# NAV_Doska_1.net
KiCad netlist of a schematic drawn in EAGLE
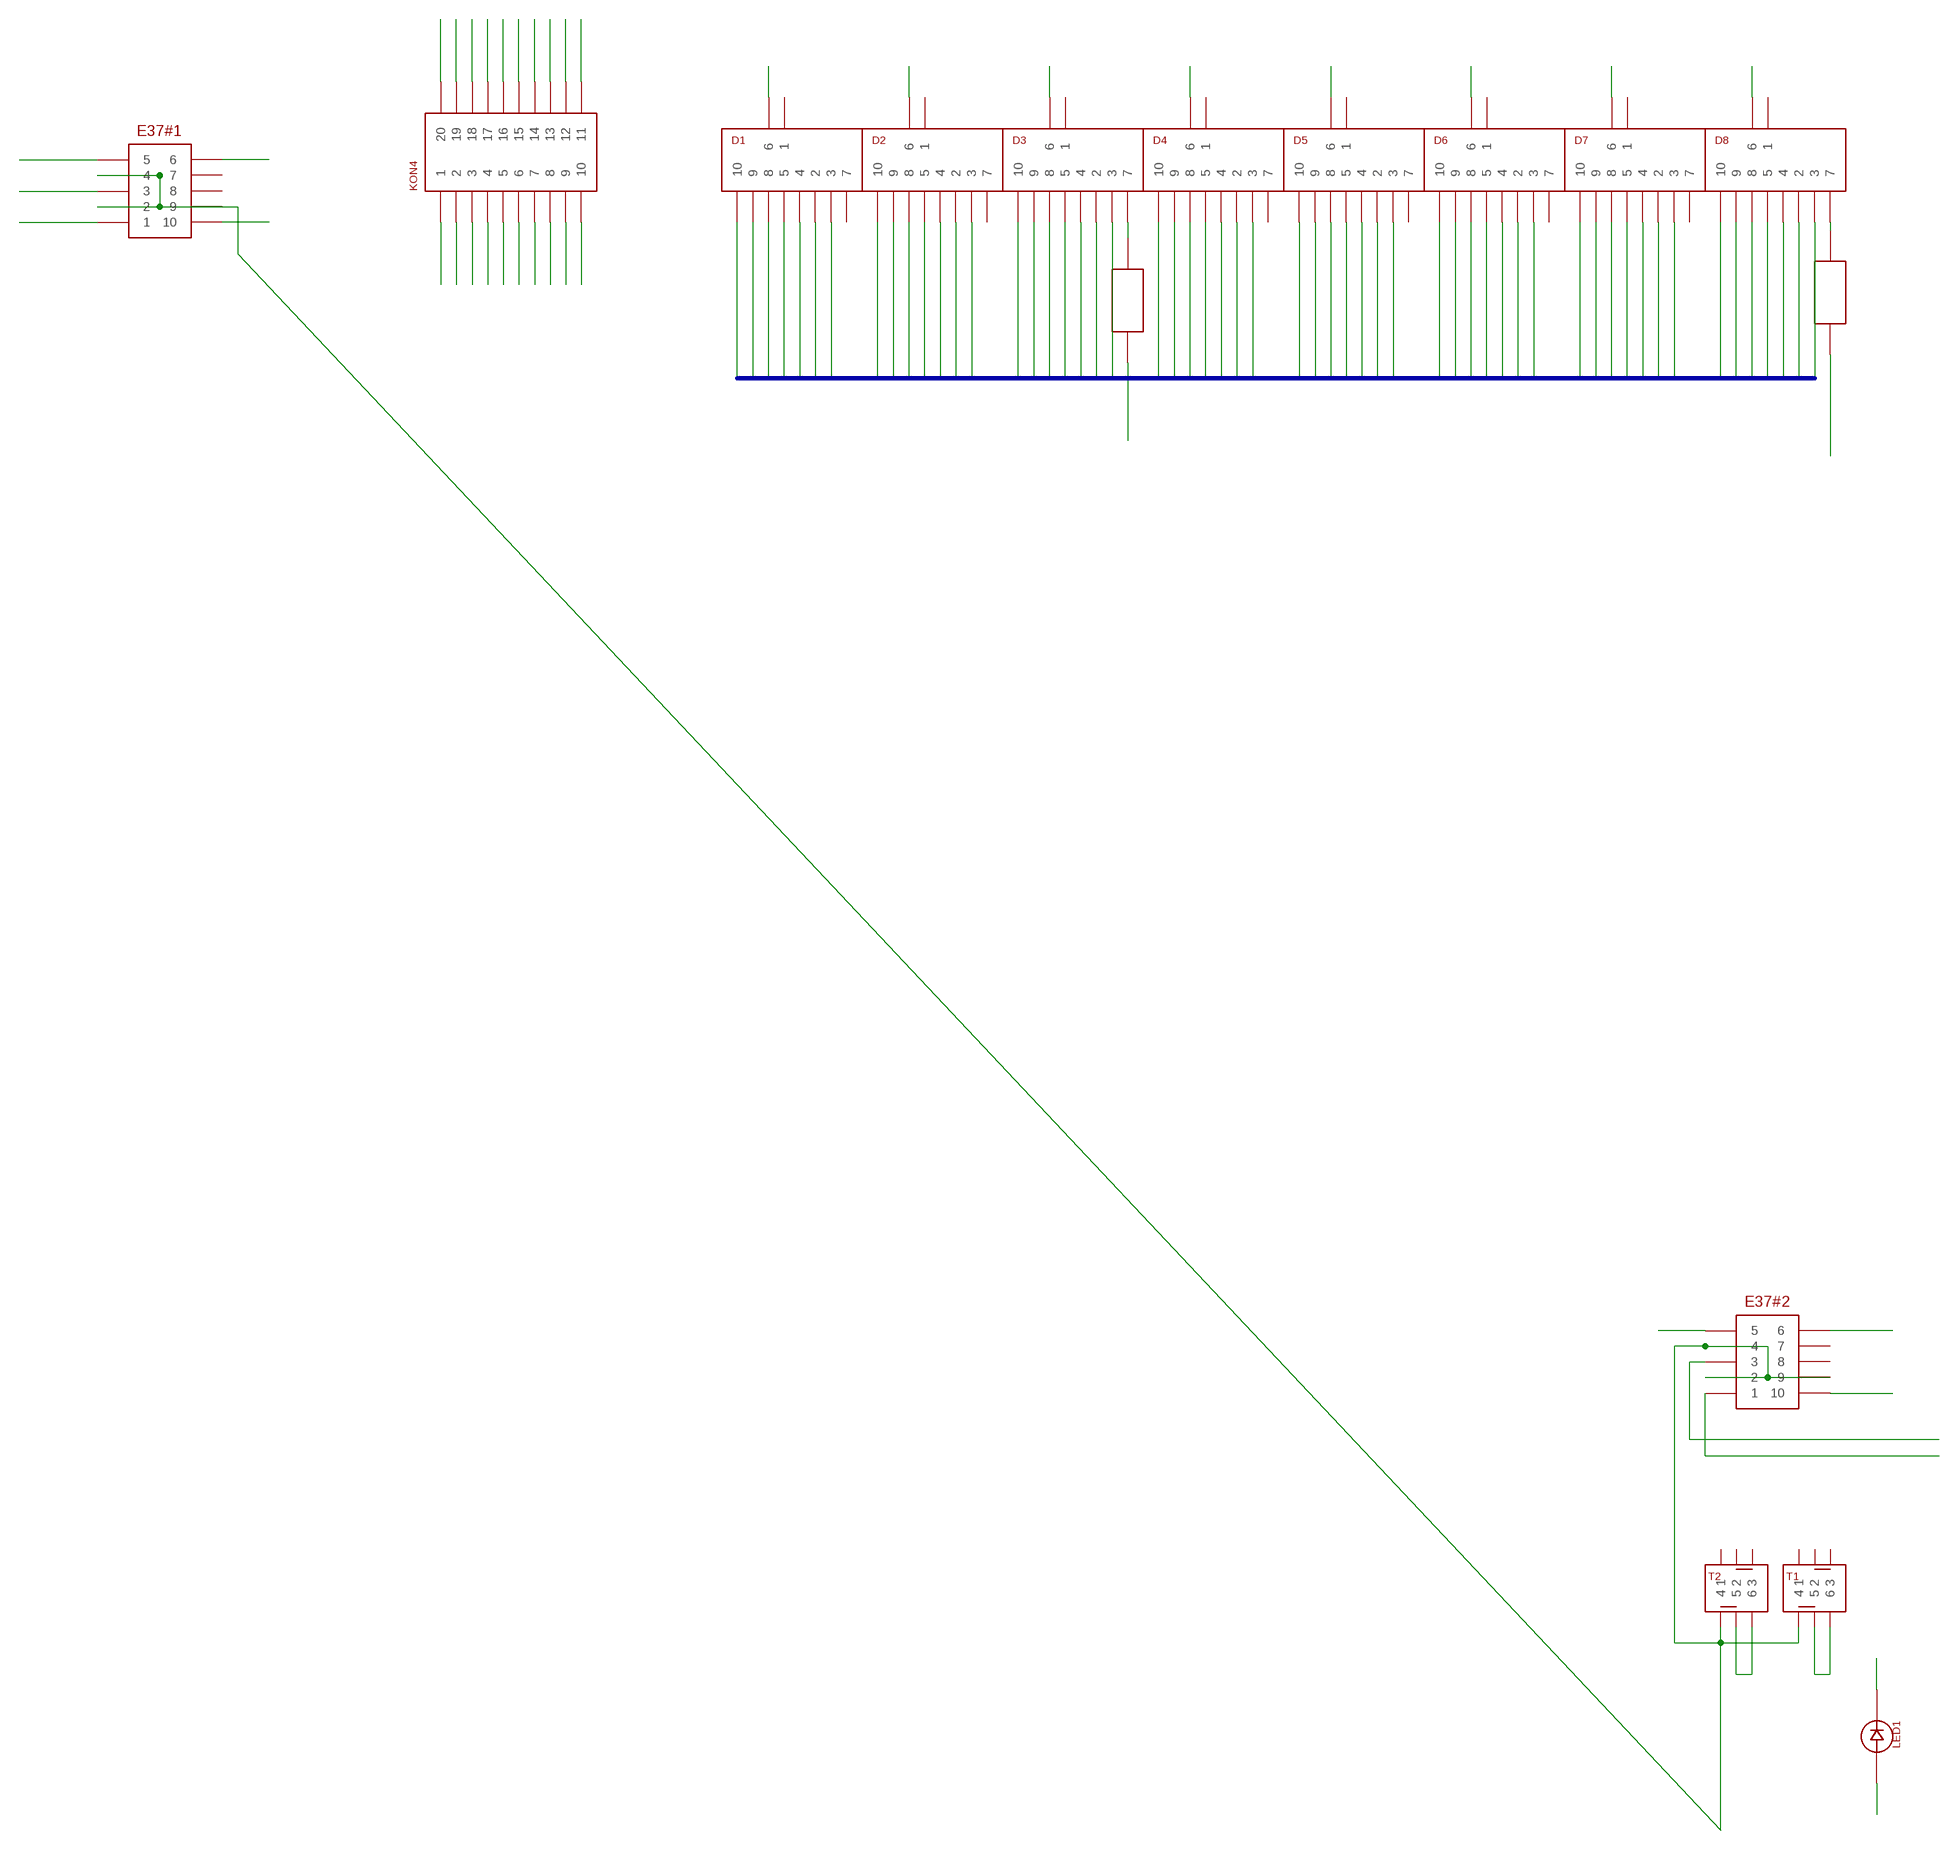
[diagram p0: schematic, sheet 1, part 1 of 2]
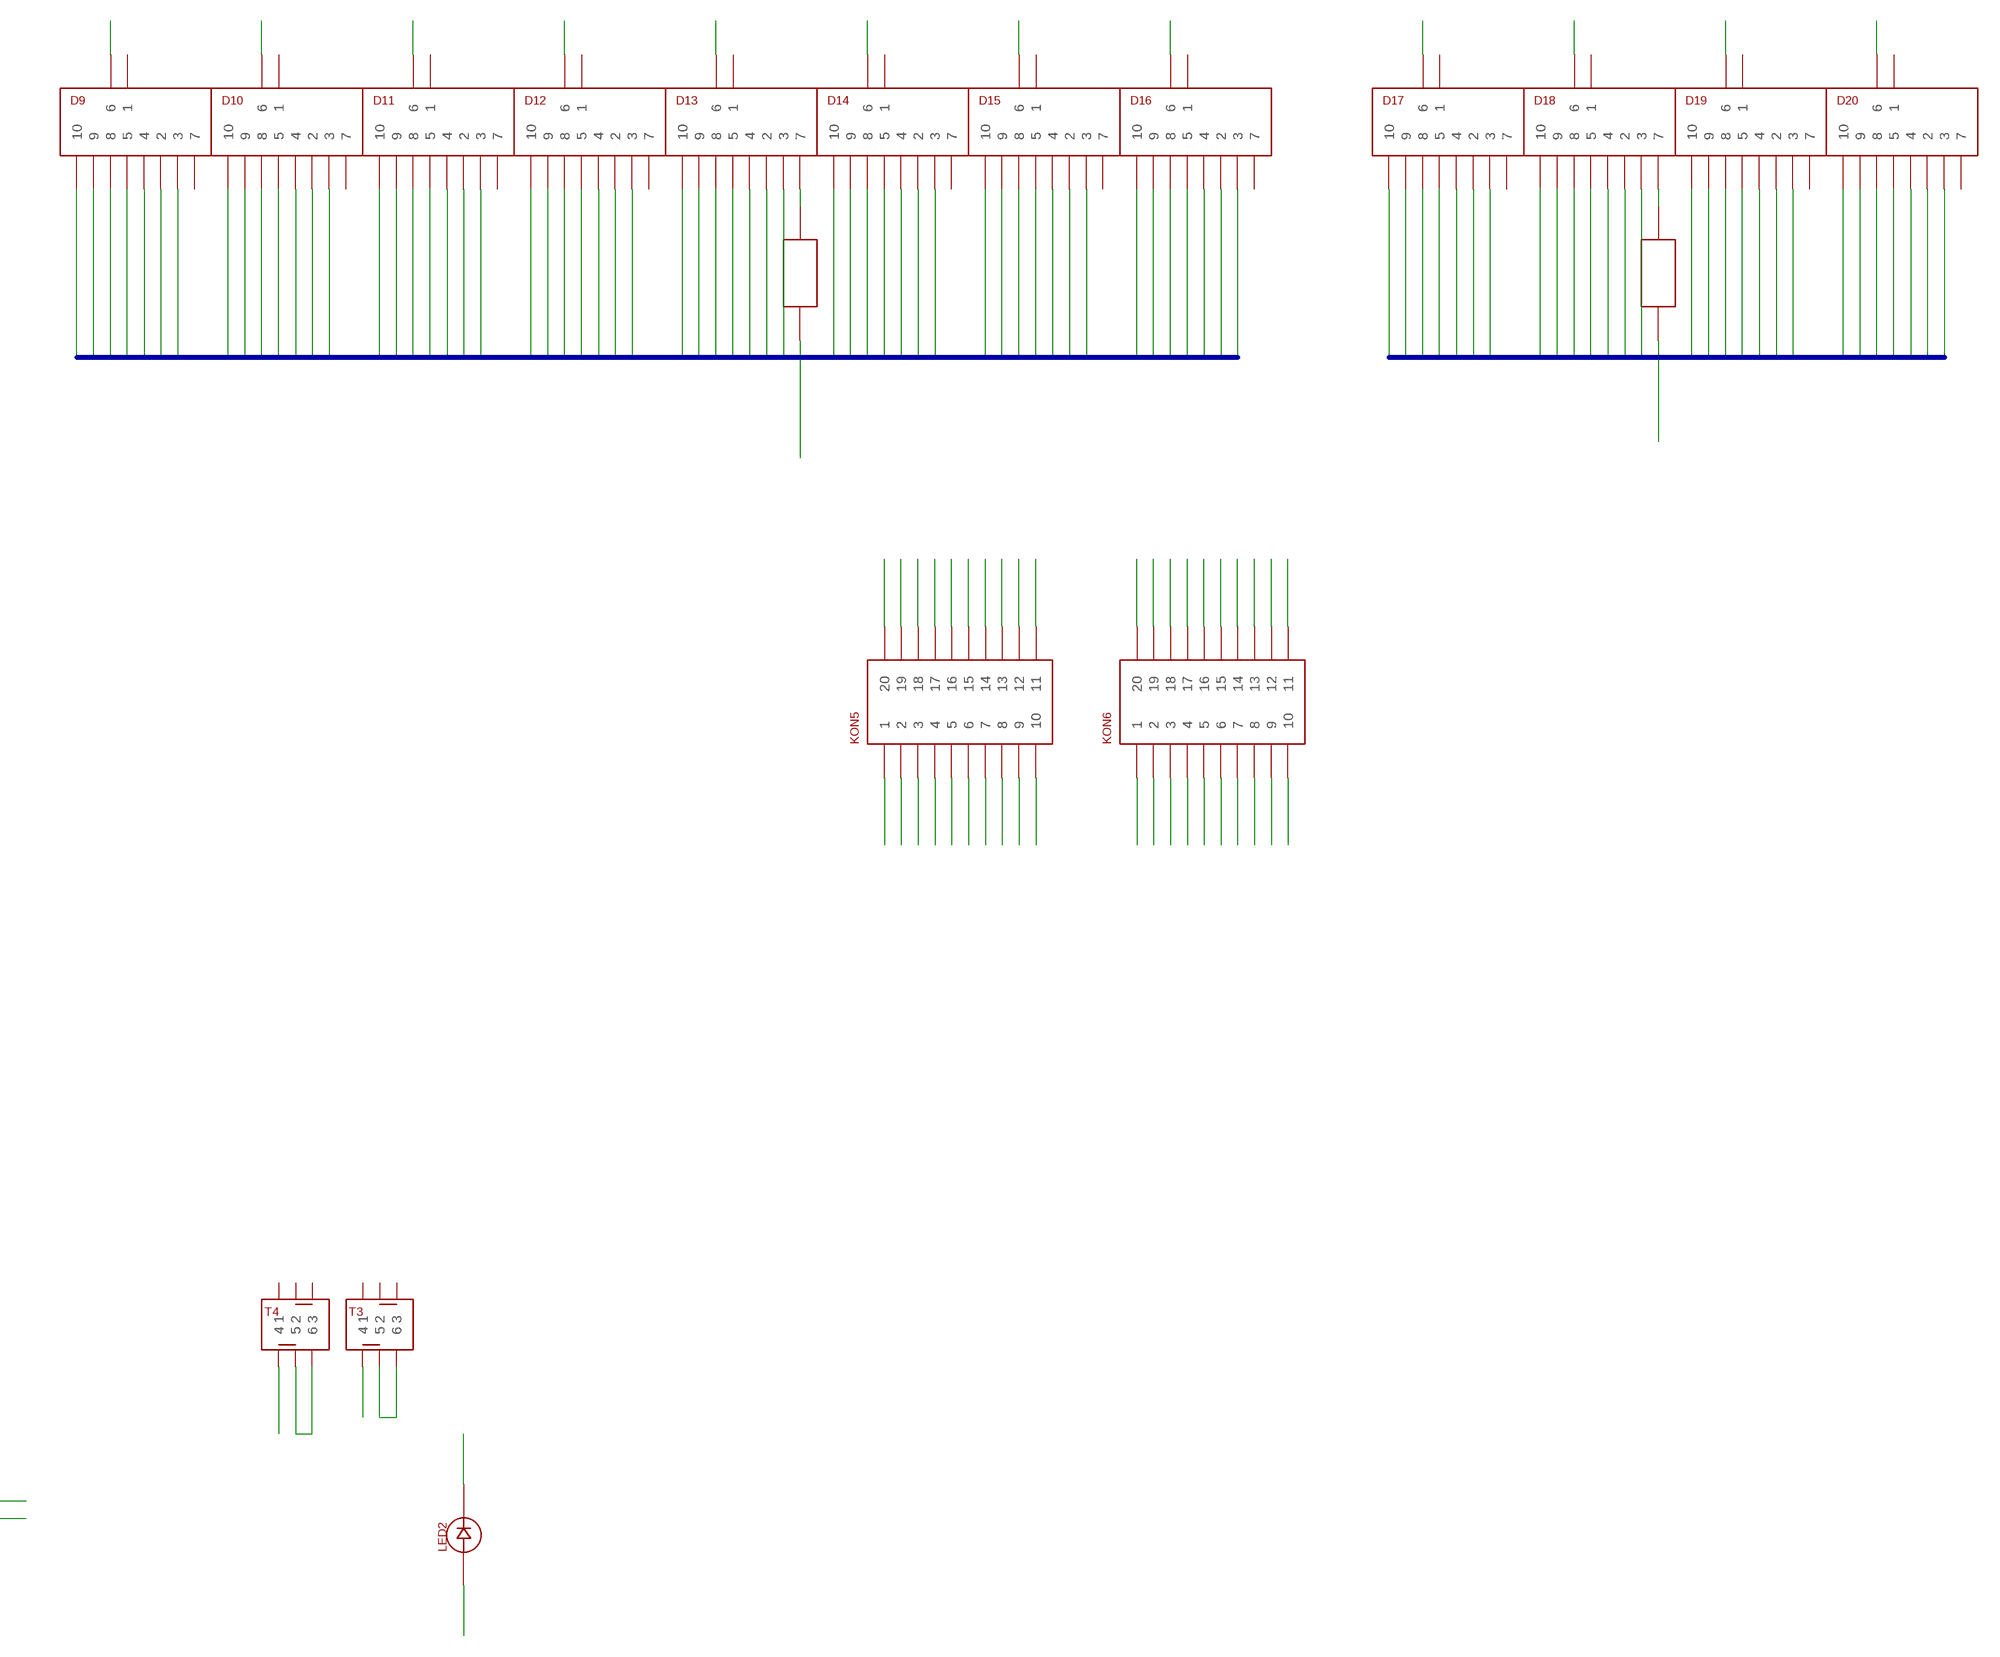
[diagram p1: schematic, sheet 1, part 2 of 2]

(export (version "E")
  (design (tool "Eeschema 10.0.6"))
  (components
    (comp (ref "D1")
      (value "SA3611EWA")
      (footprint "eagle-import:SA3611EWA")
      (libsource (lib "eagle-import") (part "SA3611EWA"))
    )
    (comp (ref "D2")
      (value "SA3611EWA")
      (footprint "eagle-import:SA3611EWA")
      (libsource (lib "eagle-import") (part "SA3611EWA"))
    )
    (comp (ref "D3")
      (value "SA3611EWA")
      (footprint "eagle-import:SA3611EWA")
      (libsource (lib "eagle-import") (part "SA3611EWA"))
    )
    (comp (ref "D4")
      (value "SA3611EWA")
      (footprint "eagle-import:SA3611EWA")
      (libsource (lib "eagle-import") (part "SA3611EWA"))
    )
    (comp (ref "D5")
      (value "SA3611EWA")
      (footprint "eagle-import:SA3611EWA")
      (libsource (lib "eagle-import") (part "SA3611EWA"))
    )
    (comp (ref "D6")
      (value "SA3611EWA")
      (footprint "eagle-import:SA3611EWA")
      (libsource (lib "eagle-import") (part "SA3611EWA"))
    )
    (comp (ref "D7")
      (value "SA3611EWA")
      (footprint "eagle-import:SA3611EWA")
      (libsource (lib "eagle-import") (part "SA3611EWA"))
    )
    (comp (ref "D8")
      (value "SA3611EWA")
      (footprint "eagle-import:SA3611EWA")
      (libsource (lib "eagle-import") (part "SA3611EWA"))
    )
    (comp (ref "D9")
      (value "SA3611EWA")
      (footprint "eagle-import:SA3611EWA")
      (libsource (lib "eagle-import") (part "SA3611EWA"))
    )
    (comp (ref "D10")
      (value "SA3611EWA")
      (footprint "eagle-import:SA3611EWA")
      (libsource (lib "eagle-import") (part "SA3611EWA"))
    )
    (comp (ref "D11")
      (value "SA3611EWA")
      (footprint "eagle-import:SA3611EWA")
      (libsource (lib "eagle-import") (part "SA3611EWA"))
    )
    (comp (ref "D12")
      (value "SA3611EWA")
      (footprint "eagle-import:SA3611EWA")
      (libsource (lib "eagle-import") (part "SA3611EWA"))
    )
    (comp (ref "D13")
      (value "SA3611EWA")
      (footprint "eagle-import:SA3611EWA")
      (libsource (lib "eagle-import") (part "SA3611EWA"))
    )
    (comp (ref "D14")
      (value "SA3611EWA")
      (footprint "eagle-import:SA3611EWA")
      (libsource (lib "eagle-import") (part "SA3611EWA"))
    )
    (comp (ref "D15")
      (value "SA3611EWA")
      (footprint "eagle-import:SA3611EWA")
      (libsource (lib "eagle-import") (part "SA3611EWA"))
    )
    (comp (ref "D16")
      (value "SA3611EWA")
      (footprint "eagle-import:SA3611EWA")
      (libsource (lib "eagle-import") (part "SA3611EWA"))
    )
    (comp (ref "D17")
      (value "SA3611EWA")
      (footprint "eagle-import:SA3611EWA")
      (libsource (lib "eagle-import") (part "SA3611EWA"))
    )
    (comp (ref "D18")
      (value "SA3611EWA")
      (footprint "eagle-import:SA3611EWA")
      (libsource (lib "eagle-import") (part "SA3611EWA"))
    )
    (comp (ref "D19")
      (value "SA3611EWA")
      (footprint "eagle-import:SA3611EWA")
      (libsource (lib "eagle-import") (part "SA3611EWA"))
    )
    (comp (ref "D20")
      (value "SA3611EWA")
      (footprint "eagle-import:SA3611EWA")
      (libsource (lib "eagle-import") (part "SA3611EWA"))
    )
    (comp (ref "E37#1")
      (value "ELMA_E37")
      (footprint "eagle-import:ELMA_E37")
      (libsource (lib "eagle-import") (part "ELMA_E37"))
    )
    (comp (ref "E37#2")
      (value "ELMA_E37")
      (footprint "eagle-import:ELMA_E37")
      (libsource (lib "eagle-import") (part "ELMA_E37"))
    )
    (comp (ref "KON4")
      (value "LISTA_2X10")
      (footprint "eagle-import:LISTA_2X10")
      (libsource (lib "eagle-import") (part "LISTA_2X10"))
    )
    (comp (ref "KON5")
      (value "LISTA_2X10")
      (footprint "eagle-import:LISTA_2X10")
      (libsource (lib "eagle-import") (part "LISTA_2X10"))
    )
    (comp (ref "KON6")
      (value "LISTA_2X10")
      (footprint "eagle-import:LISTA_2X10")
      (libsource (lib "eagle-import") (part "LISTA_2X10"))
    )
    (comp (ref "LED1")
      (value "LED_5MM")
      (footprint "eagle-import:LED_5MM")
      (libsource (lib "eagle-import") (part "LED_5MM"))
    )
    (comp (ref "LED2")
      (value "LED_5MM")
      (footprint "eagle-import:LED_5MM")
      (libsource (lib "eagle-import") (part "LED_5MM"))
    )
    (comp (ref "T1")
      (value "P1-0S")
      (footprint "eagle-import:P1-0S")
      (libsource (lib "eagle-import") (part "P1-0S"))
    )
    (comp (ref "T2")
      (value "P1-0S")
      (footprint "eagle-import:P1-0S")
      (libsource (lib "eagle-import") (part "P1-0S"))
    )
    (comp (ref "T3")
      (value "P1-0S")
      (footprint "eagle-import:P1-0S")
      (libsource (lib "eagle-import") (part "P1-0S"))
    )
    (comp (ref "T4")
      (value "P1-0S")
      (footprint "eagle-import:P1-0S")
      (libsource (lib "eagle-import") (part "P1-0S"))
    )
    (comp (ref "U$1")
      (value "REZISTOR")
      (footprint "eagle-import:REZISTOR")
      (libsource (lib "eagle-import") (part "REZISTOR"))
    )
    (comp (ref "U$2")
      (value "REZISTOR")
      (footprint "eagle-import:REZISTOR")
      (libsource (lib "eagle-import") (part "REZISTOR"))
    )
    (comp (ref "U$3")
      (value "REZISTOR")
      (footprint "eagle-import:REZISTOR")
      (libsource (lib "eagle-import") (part "REZISTOR"))
    )
    (comp (ref "U$4")
      (value "REZISTOR")
      (footprint "eagle-import:REZISTOR")
      (libsource (lib "eagle-import") (part "REZISTOR"))
    )
  )
  (nets
    (net (code "1") (name "/D1") (class "Default")
      (node (ref "D1") (pin "6") (pinfunction "6_6") (pintype "bidirectional"))
      (node (ref "KON4") (pin "1") (pinfunction "1_1") (pintype "bidirectional"))
    )
    (net (code "2") (name "/D2") (class "Default")
      (node (ref "D2") (pin "6") (pinfunction "6_6") (pintype "bidirectional"))
      (node (ref "KON4") (pin "2") (pinfunction "2_2") (pintype "bidirectional"))
    )
    (net (code "3") (name "/D3") (class "Default")
      (node (ref "D3") (pin "6") (pinfunction "6_6") (pintype "bidirectional"))
      (node (ref "KON4") (pin "9") (pinfunction "9_9") (pintype "bidirectional"))
    )
    (net (code "4") (name "/D4") (class "Default")
      (node (ref "D4") (pin "6") (pinfunction "6_6") (pintype "bidirectional"))
      (node (ref "KON4") (pin "6") (pinfunction "6_6") (pintype "bidirectional"))
    )
    (net (code "5") (name "/D5") (class "Default")
      (node (ref "D5") (pin "6") (pinfunction "6_6") (pintype "bidirectional"))
      (node (ref "KON4") (pin "3") (pinfunction "3_3") (pintype "bidirectional"))
    )
    (net (code "6") (name "/D6") (class "Default")
      (node (ref "D6") (pin "6") (pinfunction "6_6") (pintype "bidirectional"))
      (node (ref "KON4") (pin "8") (pinfunction "8_8") (pintype "bidirectional"))
    )
    (net (code "7") (name "/D7") (class "Default")
      (node (ref "D7") (pin "6") (pinfunction "6_6") (pintype "bidirectional"))
      (node (ref "KON4") (pin "7") (pinfunction "7_7") (pintype "bidirectional"))
    )
    (net (code "8") (name "/D8") (class "Default")
      (node (ref "D8") (pin "6") (pinfunction "6_6") (pintype "bidirectional"))
      (node (ref "KON4") (pin "4") (pinfunction "4_4") (pintype "bidirectional"))
    )
    (net (code "9") (name "/D9") (class "Default")
      (node (ref "D9") (pin "6") (pinfunction "6_6") (pintype "bidirectional"))
      (node (ref "KON5") (pin "1") (pinfunction "1_1") (pintype "bidirectional"))
    )
    (net (code "10") (name "/D10") (class "Default")
      (node (ref "D10") (pin "6") (pinfunction "6_6") (pintype "bidirectional"))
      (node (ref "KON5") (pin "2") (pinfunction "2_2") (pintype "bidirectional"))
    )
    (net (code "11") (name "/D11") (class "Default")
      (node (ref "D11") (pin "6") (pinfunction "6_6") (pintype "bidirectional"))
      (node (ref "KON5") (pin "9") (pinfunction "9_9") (pintype "bidirectional"))
    )
    (net (code "12") (name "/D12") (class "Default")
      (node (ref "D12") (pin "6") (pinfunction "6_6") (pintype "bidirectional"))
      (node (ref "KON5") (pin "6") (pinfunction "6_6") (pintype "bidirectional"))
    )
    (net (code "13") (name "/D13") (class "Default")
      (node (ref "D13") (pin "6") (pinfunction "6_6") (pintype "bidirectional"))
      (node (ref "KON5") (pin "3") (pinfunction "3_3") (pintype "bidirectional"))
    )
    (net (code "14") (name "/D14") (class "Default")
      (node (ref "D14") (pin "6") (pinfunction "6_6") (pintype "bidirectional"))
      (node (ref "KON5") (pin "8") (pinfunction "8_8") (pintype "bidirectional"))
    )
    (net (code "15") (name "/D15") (class "Default")
      (node (ref "D15") (pin "6") (pinfunction "6_6") (pintype "bidirectional"))
      (node (ref "KON5") (pin "7") (pinfunction "7_7") (pintype "bidirectional"))
    )
    (net (code "16") (name "/D16") (class "Default")
      (node (ref "D16") (pin "6") (pinfunction "6_6") (pintype "bidirectional"))
      (node (ref "KON5") (pin "4") (pinfunction "4_4") (pintype "bidirectional"))
    )
    (net (code "17") (name "/D17") (class "Default")
      (node (ref "D17") (pin "6") (pinfunction "6_6") (pintype "bidirectional"))
      (node (ref "KON6") (pin "1") (pinfunction "1_1") (pintype "bidirectional"))
    )
    (net (code "18") (name "/D18") (class "Default")
      (node (ref "D18") (pin "6") (pinfunction "6_6") (pintype "bidirectional"))
      (node (ref "KON6") (pin "2") (pinfunction "2_2") (pintype "bidirectional"))
    )
    (net (code "19") (name "/D19") (class "Default")
      (node (ref "D19") (pin "6") (pinfunction "6_6") (pintype "bidirectional"))
      (node (ref "KON6") (pin "9") (pinfunction "9_9") (pintype "bidirectional"))
    )
    (net (code "20") (name "/D20") (class "Default")
      (node (ref "D20") (pin "6") (pinfunction "6_6") (pintype "bidirectional"))
      (node (ref "KON6") (pin "6") (pinfunction "6_6") (pintype "bidirectional"))
    )
    (net (code "21") (name "/DRIVER1_SEG2") (class "Default")
      (node (ref "D1") (pin "2") (pinfunction "2_2") (pintype "bidirectional"))
      (node (ref "D2") (pin "2") (pinfunction "2_2") (pintype "bidirectional"))
      (node (ref "D3") (pin "2") (pinfunction "2_2") (pintype "bidirectional"))
      (node (ref "D4") (pin "2") (pinfunction "2_2") (pintype "bidirectional"))
      (node (ref "D5") (pin "2") (pinfunction "2_2") (pintype "bidirectional"))
      (node (ref "D6") (pin "2") (pinfunction "2_2") (pintype "bidirectional"))
      (node (ref "D7") (pin "2") (pinfunction "2_2") (pintype "bidirectional"))
      (node (ref "D8") (pin "2") (pinfunction "2_2") (pintype "bidirectional"))
      (node (ref "KON4") (pin "10") (pinfunction "10_10") (pintype "bidirectional"))
    )
    (net (code "22") (name "/DRIVER1_SEG3") (class "Default")
      (node (ref "D1") (pin "3") (pinfunction "3_3") (pintype "bidirectional"))
      (node (ref "D2") (pin "3") (pinfunction "3_3") (pintype "bidirectional"))
      (node (ref "D3") (pin "3") (pinfunction "3_3") (pintype "bidirectional"))
      (node (ref "D4") (pin "3") (pinfunction "3_3") (pintype "bidirectional"))
      (node (ref "D5") (pin "3") (pinfunction "3_3") (pintype "bidirectional"))
      (node (ref "D6") (pin "3") (pinfunction "3_3") (pintype "bidirectional"))
      (node (ref "D7") (pin "3") (pinfunction "3_3") (pintype "bidirectional"))
      (node (ref "D8") (pin "3") (pinfunction "3_3") (pintype "bidirectional"))
      (node (ref "KON4") (pin "12") (pinfunction "12_12") (pintype "bidirectional"))
    )
    (net (code "23") (name "/DRIVER1_SEG4") (class "Default")
      (node (ref "D1") (pin "4") (pinfunction "4_4") (pintype "bidirectional"))
      (node (ref "D2") (pin "4") (pinfunction "4_4") (pintype "bidirectional"))
      (node (ref "D3") (pin "4") (pinfunction "4_4") (pintype "bidirectional"))
      (node (ref "D4") (pin "4") (pinfunction "4_4") (pintype "bidirectional"))
      (node (ref "D5") (pin "4") (pinfunction "4_4") (pintype "bidirectional"))
      (node (ref "D6") (pin "4") (pinfunction "4_4") (pintype "bidirectional"))
      (node (ref "D7") (pin "4") (pinfunction "4_4") (pintype "bidirectional"))
      (node (ref "D8") (pin "4") (pinfunction "4_4") (pintype "bidirectional"))
      (node (ref "KON4") (pin "15") (pinfunction "15_15") (pintype "bidirectional"))
    )
    (net (code "24") (name "/DRIVER1_SEG5") (class "Default")
      (node (ref "D1") (pin "5") (pinfunction "5_5") (pintype "bidirectional"))
      (node (ref "D2") (pin "5") (pinfunction "5_5") (pintype "bidirectional"))
      (node (ref "D3") (pin "5") (pinfunction "5_5") (pintype "bidirectional"))
      (node (ref "D4") (pin "5") (pinfunction "5_5") (pintype "bidirectional"))
      (node (ref "D5") (pin "5") (pinfunction "5_5") (pintype "bidirectional"))
      (node (ref "D6") (pin "5") (pinfunction "5_5") (pintype "bidirectional"))
      (node (ref "D7") (pin "5") (pinfunction "5_5") (pintype "bidirectional"))
      (node (ref "D8") (pin "5") (pinfunction "5_5") (pintype "bidirectional"))
      (node (ref "KON4") (pin "16") (pinfunction "16_16") (pintype "bidirectional"))
    )
    (net (code "25") (name "/DRIVER1_SEG8") (class "Default")
      (node (ref "D1") (pin "8") (pinfunction "8_8") (pintype "bidirectional"))
      (node (ref "D2") (pin "8") (pinfunction "8_8") (pintype "bidirectional"))
      (node (ref "D3") (pin "8") (pinfunction "8_8") (pintype "bidirectional"))
      (node (ref "D4") (pin "8") (pinfunction "8_8") (pintype "bidirectional"))
      (node (ref "D5") (pin "8") (pinfunction "8_8") (pintype "bidirectional"))
      (node (ref "D6") (pin "8") (pinfunction "8_8") (pintype "bidirectional"))
      (node (ref "D7") (pin "8") (pinfunction "8_8") (pintype "bidirectional"))
      (node (ref "D8") (pin "8") (pinfunction "8_8") (pintype "bidirectional"))
      (node (ref "KON4") (pin "14") (pinfunction "14_14") (pintype "bidirectional"))
    )
    (net (code "26") (name "/DRIVER1_SEG9") (class "Default")
      (node (ref "D1") (pin "9") (pinfunction "9_9") (pintype "bidirectional"))
      (node (ref "D2") (pin "9") (pinfunction "9_9") (pintype "bidirectional"))
      (node (ref "D3") (pin "9") (pinfunction "9_9") (pintype "bidirectional"))
      (node (ref "D4") (pin "9") (pinfunction "9_9") (pintype "bidirectional"))
      (node (ref "D5") (pin "9") (pinfunction "9_9") (pintype "bidirectional"))
      (node (ref "D6") (pin "9") (pinfunction "9_9") (pintype "bidirectional"))
      (node (ref "D7") (pin "9") (pinfunction "9_9") (pintype "bidirectional"))
      (node (ref "D8") (pin "9") (pinfunction "9_9") (pintype "bidirectional"))
      (node (ref "KON4") (pin "11") (pinfunction "11_11") (pintype "bidirectional"))
    )
    (net (code "27") (name "/DRIVER1_SEG10") (class "Default")
      (node (ref "D1") (pin "10") (pinfunction "10_10") (pintype "bidirectional"))
      (node (ref "D2") (pin "10") (pinfunction "10_10") (pintype "bidirectional"))
      (node (ref "D3") (pin "10") (pinfunction "10_10") (pintype "bidirectional"))
      (node (ref "D4") (pin "10") (pinfunction "10_10") (pintype "bidirectional"))
      (node (ref "D5") (pin "10") (pinfunction "10_10") (pintype "bidirectional"))
      (node (ref "D6") (pin "10") (pinfunction "10_10") (pintype "bidirectional"))
      (node (ref "D7") (pin "10") (pinfunction "10_10") (pintype "bidirectional"))
      (node (ref "D8") (pin "10") (pinfunction "10_10") (pintype "bidirectional"))
      (node (ref "KON4") (pin "13") (pinfunction "13_13") (pintype "bidirectional"))
    )
    (net (code "28") (name "/DRIVER2_SEG2") (class "Default")
      (node (ref "D10") (pin "2") (pinfunction "2_2") (pintype "bidirectional"))
      (node (ref "D11") (pin "2") (pinfunction "2_2") (pintype "bidirectional"))
      (node (ref "D12") (pin "2") (pinfunction "2_2") (pintype "bidirectional"))
      (node (ref "D13") (pin "2") (pinfunction "2_2") (pintype "bidirectional"))
      (node (ref "D14") (pin "2") (pinfunction "2_2") (pintype "bidirectional"))
      (node (ref "D15") (pin "2") (pinfunction "2_2") (pintype "bidirectional"))
      (node (ref "D16") (pin "2") (pinfunction "2_2") (pintype "bidirectional"))
      (node (ref "D9") (pin "2") (pinfunction "2_2") (pintype "bidirectional"))
      (node (ref "KON5") (pin "10") (pinfunction "10_10") (pintype "bidirectional"))
    )
    (net (code "29") (name "/DRIVER2_SEG3") (class "Default")
      (node (ref "D10") (pin "3") (pinfunction "3_3") (pintype "bidirectional"))
      (node (ref "D11") (pin "3") (pinfunction "3_3") (pintype "bidirectional"))
      (node (ref "D12") (pin "3") (pinfunction "3_3") (pintype "bidirectional"))
      (node (ref "D13") (pin "3") (pinfunction "3_3") (pintype "bidirectional"))
      (node (ref "D14") (pin "3") (pinfunction "3_3") (pintype "bidirectional"))
      (node (ref "D15") (pin "3") (pinfunction "3_3") (pintype "bidirectional"))
      (node (ref "D16") (pin "3") (pinfunction "3_3") (pintype "bidirectional"))
      (node (ref "D9") (pin "3") (pinfunction "3_3") (pintype "bidirectional"))
      (node (ref "KON5") (pin "12") (pinfunction "12_12") (pintype "bidirectional"))
    )
    (net (code "30") (name "/DRIVER2_SEG4") (class "Default")
      (node (ref "D10") (pin "4") (pinfunction "4_4") (pintype "bidirectional"))
      (node (ref "D11") (pin "4") (pinfunction "4_4") (pintype "bidirectional"))
      (node (ref "D12") (pin "4") (pinfunction "4_4") (pintype "bidirectional"))
      (node (ref "D13") (pin "4") (pinfunction "4_4") (pintype "bidirectional"))
      (node (ref "D14") (pin "4") (pinfunction "4_4") (pintype "bidirectional"))
      (node (ref "D15") (pin "4") (pinfunction "4_4") (pintype "bidirectional"))
      (node (ref "D16") (pin "4") (pinfunction "4_4") (pintype "bidirectional"))
      (node (ref "D9") (pin "4") (pinfunction "4_4") (pintype "bidirectional"))
      (node (ref "KON5") (pin "15") (pinfunction "15_15") (pintype "bidirectional"))
    )
    (net (code "31") (name "/DRIVER2_SEG5") (class "Default")
      (node (ref "D10") (pin "5") (pinfunction "5_5") (pintype "bidirectional"))
      (node (ref "D11") (pin "5") (pinfunction "5_5") (pintype "bidirectional"))
      (node (ref "D12") (pin "5") (pinfunction "5_5") (pintype "bidirectional"))
      (node (ref "D13") (pin "5") (pinfunction "5_5") (pintype "bidirectional"))
      (node (ref "D14") (pin "5") (pinfunction "5_5") (pintype "bidirectional"))
      (node (ref "D15") (pin "5") (pinfunction "5_5") (pintype "bidirectional"))
      (node (ref "D16") (pin "5") (pinfunction "5_5") (pintype "bidirectional"))
      (node (ref "D9") (pin "5") (pinfunction "5_5") (pintype "bidirectional"))
      (node (ref "KON5") (pin "16") (pinfunction "16_16") (pintype "bidirectional"))
    )
    (net (code "32") (name "/DRIVER2_SEG8") (class "Default")
      (node (ref "D10") (pin "8") (pinfunction "8_8") (pintype "bidirectional"))
      (node (ref "D11") (pin "8") (pinfunction "8_8") (pintype "bidirectional"))
      (node (ref "D12") (pin "8") (pinfunction "8_8") (pintype "bidirectional"))
      (node (ref "D13") (pin "8") (pinfunction "8_8") (pintype "bidirectional"))
      (node (ref "D14") (pin "8") (pinfunction "8_8") (pintype "bidirectional"))
      (node (ref "D15") (pin "8") (pinfunction "8_8") (pintype "bidirectional"))
      (node (ref "D16") (pin "8") (pinfunction "8_8") (pintype "bidirectional"))
      (node (ref "D9") (pin "8") (pinfunction "8_8") (pintype "bidirectional"))
      (node (ref "KON5") (pin "14") (pinfunction "14_14") (pintype "bidirectional"))
    )
    (net (code "33") (name "/DRIVER2_SEG9") (class "Default")
      (node (ref "D10") (pin "9") (pinfunction "9_9") (pintype "bidirectional"))
      (node (ref "D11") (pin "9") (pinfunction "9_9") (pintype "bidirectional"))
      (node (ref "D12") (pin "9") (pinfunction "9_9") (pintype "bidirectional"))
      (node (ref "D13") (pin "9") (pinfunction "9_9") (pintype "bidirectional"))
      (node (ref "D14") (pin "9") (pinfunction "9_9") (pintype "bidirectional"))
      (node (ref "D15") (pin "9") (pinfunction "9_9") (pintype "bidirectional"))
      (node (ref "D16") (pin "9") (pinfunction "9_9") (pintype "bidirectional"))
      (node (ref "D9") (pin "9") (pinfunction "9_9") (pintype "bidirectional"))
      (node (ref "KON5") (pin "11") (pinfunction "11_11") (pintype "bidirectional"))
    )
    (net (code "34") (name "/DRIVER2_SEG10") (class "Default")
      (node (ref "D10") (pin "10") (pinfunction "10_10") (pintype "bidirectional"))
      (node (ref "D11") (pin "10") (pinfunction "10_10") (pintype "bidirectional"))
      (node (ref "D12") (pin "10") (pinfunction "10_10") (pintype "bidirectional"))
      (node (ref "D13") (pin "10") (pinfunction "10_10") (pintype "bidirectional"))
      (node (ref "D14") (pin "10") (pinfunction "10_10") (pintype "bidirectional"))
      (node (ref "D15") (pin "10") (pinfunction "10_10") (pintype "bidirectional"))
      (node (ref "D16") (pin "10") (pinfunction "10_10") (pintype "bidirectional"))
      (node (ref "D9") (pin "10") (pinfunction "10_10") (pintype "bidirectional"))
      (node (ref "KON5") (pin "13") (pinfunction "13_13") (pintype "bidirectional"))
    )
    (net (code "35") (name "/DRIVER3_SEG2") (class "Default")
      (node (ref "D17") (pin "2") (pinfunction "2_2") (pintype "bidirectional"))
      (node (ref "D18") (pin "2") (pinfunction "2_2") (pintype "bidirectional"))
      (node (ref "D19") (pin "2") (pinfunction "2_2") (pintype "bidirectional"))
      (node (ref "D20") (pin "2") (pinfunction "2_2") (pintype "bidirectional"))
      (node (ref "KON6") (pin "10") (pinfunction "10_10") (pintype "bidirectional"))
    )
    (net (code "36") (name "/DRIVER3_SEG3") (class "Default")
      (node (ref "D17") (pin "3") (pinfunction "3_3") (pintype "bidirectional"))
      (node (ref "D18") (pin "3") (pinfunction "3_3") (pintype "bidirectional"))
      (node (ref "D19") (pin "3") (pinfunction "3_3") (pintype "bidirectional"))
      (node (ref "D20") (pin "3") (pinfunction "3_3") (pintype "bidirectional"))
      (node (ref "KON6") (pin "12") (pinfunction "12_12") (pintype "bidirectional"))
    )
    (net (code "37") (name "/DRIVER3_SEG4") (class "Default")
      (node (ref "D17") (pin "4") (pinfunction "4_4") (pintype "bidirectional"))
      (node (ref "D18") (pin "4") (pinfunction "4_4") (pintype "bidirectional"))
      (node (ref "D19") (pin "4") (pinfunction "4_4") (pintype "bidirectional"))
      (node (ref "D20") (pin "4") (pinfunction "4_4") (pintype "bidirectional"))
      (node (ref "KON6") (pin "15") (pinfunction "15_15") (pintype "bidirectional"))
    )
    (net (code "38") (name "/DRIVER3_SEG5") (class "Default")
      (node (ref "D17") (pin "5") (pinfunction "5_5") (pintype "bidirectional"))
      (node (ref "D18") (pin "5") (pinfunction "5_5") (pintype "bidirectional"))
      (node (ref "D19") (pin "5") (pinfunction "5_5") (pintype "bidirectional"))
      (node (ref "D20") (pin "5") (pinfunction "5_5") (pintype "bidirectional"))
      (node (ref "KON6") (pin "16") (pinfunction "16_16") (pintype "bidirectional"))
      (node (ref "LED1") (pin "P$2") (pinfunction "P$2_P$2") (pintype "bidirectional"))
      (node (ref "LED2") (pin "P$2") (pinfunction "P$2_P$2") (pintype "bidirectional"))
    )
    (net (code "39") (name "/DRIVER3_SEG8") (class "Default")
      (node (ref "D17") (pin "8") (pinfunction "8_8") (pintype "bidirectional"))
      (node (ref "D18") (pin "8") (pinfunction "8_8") (pintype "bidirectional"))
      (node (ref "D19") (pin "8") (pinfunction "8_8") (pintype "bidirectional"))
      (node (ref "D20") (pin "8") (pinfunction "8_8") (pintype "bidirectional"))
      (node (ref "KON6") (pin "14") (pinfunction "14_14") (pintype "bidirectional"))
    )
    (net (code "40") (name "/DRIVER3_SEG9") (class "Default")
      (node (ref "D17") (pin "9") (pinfunction "9_9") (pintype "bidirectional"))
      (node (ref "D18") (pin "9") (pinfunction "9_9") (pintype "bidirectional"))
      (node (ref "D19") (pin "9") (pinfunction "9_9") (pintype "bidirectional"))
      (node (ref "D20") (pin "9") (pinfunction "9_9") (pintype "bidirectional"))
      (node (ref "KON6") (pin "11") (pinfunction "11_11") (pintype "bidirectional"))
    )
    (net (code "41") (name "/DRIVER3_SEG10") (class "Default")
      (node (ref "D17") (pin "10") (pinfunction "10_10") (pintype "bidirectional"))
      (node (ref "D18") (pin "10") (pinfunction "10_10") (pintype "bidirectional"))
      (node (ref "D19") (pin "10") (pinfunction "10_10") (pintype "bidirectional"))
      (node (ref "D20") (pin "10") (pinfunction "10_10") (pintype "bidirectional"))
      (node (ref "KON6") (pin "13") (pinfunction "13_13") (pintype "bidirectional"))
    )
    (net (code "42") (name "/E37#1_1") (class "Default")
      (node (ref "E37#1") (pin "1") (pinfunction "1_1") (pintype "bidirectional"))
      (node (ref "KON4") (pin "17") (pinfunction "17_17") (pintype "bidirectional"))
    )
    (net (code "43") (name "/E37#1_3") (class "Default")
      (node (ref "E37#1") (pin "3") (pinfunction "3_3") (pintype "bidirectional"))
      (node (ref "KON4") (pin "18") (pinfunction "18_18") (pintype "bidirectional"))
    )
    (net (code "44") (name "/E37#1_5") (class "Default")
      (node (ref "E37#1") (pin "5") (pinfunction "5_5") (pintype "bidirectional"))
      (node (ref "KON4") (pin "20") (pinfunction "20_20") (pintype "bidirectional"))
    )
    (net (code "45") (name "/E37#1_6") (class "Default")
      (node (ref "E37#1") (pin "6") (pinfunction "6_6") (pintype "bidirectional"))
      (node (ref "KON4") (pin "19") (pinfunction "19_19") (pintype "bidirectional"))
    )
    (net (code "46") (name "/E37#1_10") (class "Default")
      (node (ref "E37#1") (pin "10") (pinfunction "10_10") (pintype "bidirectional"))
      (node (ref "KON4") (pin "5") (pinfunction "5_5") (pintype "bidirectional"))
    )
    (net (code "47") (name "/E37#2_1") (class "Default")
      (node (ref "E37#2") (pin "1") (pinfunction "1_1") (pintype "bidirectional"))
      (node (ref "KON6") (pin "17") (pinfunction "17_17") (pintype "bidirectional"))
    )
    (net (code "48") (name "/E37#2_3") (class "Default")
      (node (ref "E37#2") (pin "3") (pinfunction "3_3") (pintype "bidirectional"))
      (node (ref "KON6") (pin "18") (pinfunction "18_18") (pintype "bidirectional"))
    )
    (net (code "49") (name "/E37#2_5") (class "Default")
      (node (ref "E37#2") (pin "5") (pinfunction "5_5") (pintype "bidirectional"))
      (node (ref "KON6") (pin "20") (pinfunction "20_20") (pintype "bidirectional"))
    )
    (net (code "50") (name "/E37#2_6") (class "Default")
      (node (ref "E37#2") (pin "6") (pinfunction "6_6") (pintype "bidirectional"))
      (node (ref "KON6") (pin "19") (pinfunction "19_19") (pintype "bidirectional"))
    )
    (net (code "51") (name "/E37#2_10") (class "Default")
      (node (ref "E37#2") (pin "10") (pinfunction "10_10") (pintype "bidirectional"))
      (node (ref "KON6") (pin "5") (pinfunction "5_5") (pintype "bidirectional"))
    )
    (net (code "52") (name "/GND") (class "Default")
      (node (ref "E37#1") (pin "2") (pinfunction "2_2") (pintype "bidirectional"))
      (node (ref "E37#1") (pin "4") (pinfunction "4_4") (pintype "bidirectional"))
      (node (ref "E37#1") (pin "9") (pinfunction "9_9") (pintype "bidirectional"))
      (node (ref "E37#2") (pin "2") (pinfunction "2_2") (pintype "bidirectional"))
      (node (ref "E37#2") (pin "4") (pinfunction "4_4") (pintype "bidirectional"))
      (node (ref "E37#2") (pin "9") (pinfunction "9_9") (pintype "bidirectional"))
      (node (ref "KON5") (pin "5") (pinfunction "5_5") (pintype "bidirectional"))
      (node (ref "T1") (pin "4") (pinfunction "4_4") (pintype "bidirectional"))
      (node (ref "T2") (pin "4") (pinfunction "4_4") (pintype "bidirectional"))
      (node (ref "T3") (pin "5") (pinfunction "5_5") (pintype "bidirectional"))
      (node (ref "T3") (pin "6") (pinfunction "6_6") (pintype "bidirectional"))
      (node (ref "T4") (pin "5") (pinfunction "5_5") (pintype "bidirectional"))
      (node (ref "T4") (pin "6") (pinfunction "6_6") (pintype "bidirectional"))
      (node (ref "U$1") (pin "P$1") (pinfunction "P$1_P$1") (pintype "bidirectional"))
      (node (ref "U$2") (pin "P$1") (pinfunction "P$1_P$1") (pintype "bidirectional"))
      (node (ref "U$3") (pin "P$1") (pinfunction "P$1_P$1") (pintype "bidirectional"))
      (node (ref "U$4") (pin "P$1") (pinfunction "P$1_P$1") (pintype "bidirectional"))
    )
    (net (code "53") (name "/LED1") (class "Default")
      (node (ref "KON6") (pin "3") (pinfunction "3_3") (pintype "bidirectional"))
      (node (ref "LED1") (pin "P$1") (pinfunction "P$1_P$1") (pintype "bidirectional"))
    )
    (net (code "54") (name "/LED2") (class "Default")
      (node (ref "KON6") (pin "8") (pinfunction "8_8") (pintype "bidirectional"))
      (node (ref "LED2") (pin "P$1") (pinfunction "P$1_P$1") (pintype "bidirectional"))
    )
    (net (code "55") (name "/T1") (class "Default")
      (node (ref "KON5") (pin "20") (pinfunction "20_20") (pintype "bidirectional"))
      (node (ref "T1") (pin "5") (pinfunction "5_5") (pintype "bidirectional"))
      (node (ref "T1") (pin "6") (pinfunction "6_6") (pintype "bidirectional"))
    )
    (net (code "56") (name "/T2") (class "Default")
      (node (ref "KON5") (pin "19") (pinfunction "19_19") (pintype "bidirectional"))
      (node (ref "T2") (pin "5") (pinfunction "5_5") (pintype "bidirectional"))
      (node (ref "T2") (pin "6") (pinfunction "6_6") (pintype "bidirectional"))
    )
    (net (code "57") (name "/T3") (class "Default")
      (node (ref "KON5") (pin "18") (pinfunction "18_18") (pintype "bidirectional"))
      (node (ref "T3") (pin "4") (pinfunction "4_4") (pintype "bidirectional"))
    )
    (net (code "58") (name "/T4") (class "Default")
      (node (ref "KON5") (pin "17") (pinfunction "17_17") (pintype "bidirectional"))
      (node (ref "T4") (pin "4") (pinfunction "4_4") (pintype "bidirectional"))
    )
    (net (code "59") (name "Net-(D3-Pad7)") (class "Default")
      (node (ref "D3") (pin "7") (pinfunction "7_7") (pintype "bidirectional"))
      (node (ref "U$4") (pin "P$2") (pinfunction "P$2_P$2") (pintype "bidirectional"))
    )
    (net (code "60") (name "Net-(D8-Pad7)") (class "Default")
      (node (ref "D8") (pin "7") (pinfunction "7_7") (pintype "bidirectional"))
      (node (ref "U$3") (pin "P$2") (pinfunction "P$2_P$2") (pintype "bidirectional"))
    )
    (net (code "61") (name "Net-(D13-Pad7)") (class "Default")
      (node (ref "D13") (pin "7") (pinfunction "7_7") (pintype "bidirectional"))
      (node (ref "U$1") (pin "P$2") (pinfunction "P$2_P$2") (pintype "bidirectional"))
    )
    (net (code "62") (name "Net-(D18-Pad7)") (class "Default")
      (node (ref "D18") (pin "7") (pinfunction "7_7") (pintype "bidirectional"))
      (node (ref "U$2") (pin "P$2") (pinfunction "P$2_P$2") (pintype "bidirectional"))
    )
    (net (code "63") (name "unconnected-(D1-Pad1)") (class "Default")
      (node (ref "D1") (pin "1") (pinfunction "1_1") (pintype "bidirectional"))
    )
    (net (code "64") (name "unconnected-(D1-Pad7)") (class "Default")
      (node (ref "D1") (pin "7") (pinfunction "7_7") (pintype "bidirectional"))
    )
    (net (code "65") (name "unconnected-(D2-Pad1)") (class "Default")
      (node (ref "D2") (pin "1") (pinfunction "1_1") (pintype "bidirectional"))
    )
    (net (code "66") (name "unconnected-(D2-Pad7)") (class "Default")
      (node (ref "D2") (pin "7") (pinfunction "7_7") (pintype "bidirectional"))
    )
    (net (code "67") (name "unconnected-(D3-Pad1)") (class "Default")
      (node (ref "D3") (pin "1") (pinfunction "1_1") (pintype "bidirectional"))
    )
    (net (code "68") (name "unconnected-(D4-Pad1)") (class "Default")
      (node (ref "D4") (pin "1") (pinfunction "1_1") (pintype "bidirectional"))
    )
    (net (code "69") (name "unconnected-(D4-Pad7)") (class "Default")
      (node (ref "D4") (pin "7") (pinfunction "7_7") (pintype "bidirectional"))
    )
    (net (code "70") (name "unconnected-(D5-Pad1)") (class "Default")
      (node (ref "D5") (pin "1") (pinfunction "1_1") (pintype "bidirectional"))
    )
    (net (code "71") (name "unconnected-(D5-Pad7)") (class "Default")
      (node (ref "D5") (pin "7") (pinfunction "7_7") (pintype "bidirectional"))
    )
    (net (code "72") (name "unconnected-(D6-Pad1)") (class "Default")
      (node (ref "D6") (pin "1") (pinfunction "1_1") (pintype "bidirectional"))
    )
    (net (code "73") (name "unconnected-(D6-Pad7)") (class "Default")
      (node (ref "D6") (pin "7") (pinfunction "7_7") (pintype "bidirectional"))
    )
    (net (code "74") (name "unconnected-(D7-Pad1)") (class "Default")
      (node (ref "D7") (pin "1") (pinfunction "1_1") (pintype "bidirectional"))
    )
    (net (code "75") (name "unconnected-(D7-Pad7)") (class "Default")
      (node (ref "D7") (pin "7") (pinfunction "7_7") (pintype "bidirectional"))
    )
    (net (code "76") (name "unconnected-(D8-Pad1)") (class "Default")
      (node (ref "D8") (pin "1") (pinfunction "1_1") (pintype "bidirectional"))
    )
    (net (code "77") (name "unconnected-(D9-Pad1)") (class "Default")
      (node (ref "D9") (pin "1") (pinfunction "1_1") (pintype "bidirectional"))
    )
    (net (code "78") (name "unconnected-(D9-Pad7)") (class "Default")
      (node (ref "D9") (pin "7") (pinfunction "7_7") (pintype "bidirectional"))
    )
    (net (code "79") (name "unconnected-(D10-Pad1)") (class "Default")
      (node (ref "D10") (pin "1") (pinfunction "1_1") (pintype "bidirectional"))
    )
    (net (code "80") (name "unconnected-(D10-Pad7)") (class "Default")
      (node (ref "D10") (pin "7") (pinfunction "7_7") (pintype "bidirectional"))
    )
    (net (code "81") (name "unconnected-(D11-Pad1)") (class "Default")
      (node (ref "D11") (pin "1") (pinfunction "1_1") (pintype "bidirectional"))
    )
    (net (code "82") (name "unconnected-(D11-Pad7)") (class "Default")
      (node (ref "D11") (pin "7") (pinfunction "7_7") (pintype "bidirectional"))
    )
    (net (code "83") (name "unconnected-(D12-Pad1)") (class "Default")
      (node (ref "D12") (pin "1") (pinfunction "1_1") (pintype "bidirectional"))
    )
    (net (code "84") (name "unconnected-(D12-Pad7)") (class "Default")
      (node (ref "D12") (pin "7") (pinfunction "7_7") (pintype "bidirectional"))
    )
    (net (code "85") (name "unconnected-(D13-Pad1)") (class "Default")
      (node (ref "D13") (pin "1") (pinfunction "1_1") (pintype "bidirectional"))
    )
    (net (code "86") (name "unconnected-(D14-Pad1)") (class "Default")
      (node (ref "D14") (pin "1") (pinfunction "1_1") (pintype "bidirectional"))
    )
    (net (code "87") (name "unconnected-(D14-Pad7)") (class "Default")
      (node (ref "D14") (pin "7") (pinfunction "7_7") (pintype "bidirectional"))
    )
    (net (code "88") (name "unconnected-(D15-Pad1)") (class "Default")
      (node (ref "D15") (pin "1") (pinfunction "1_1") (pintype "bidirectional"))
    )
    (net (code "89") (name "unconnected-(D15-Pad7)") (class "Default")
      (node (ref "D15") (pin "7") (pinfunction "7_7") (pintype "bidirectional"))
    )
    (net (code "90") (name "unconnected-(D16-Pad1)") (class "Default")
      (node (ref "D16") (pin "1") (pinfunction "1_1") (pintype "bidirectional"))
    )
    (net (code "91") (name "unconnected-(D16-Pad7)") (class "Default")
      (node (ref "D16") (pin "7") (pinfunction "7_7") (pintype "bidirectional"))
    )
    (net (code "92") (name "unconnected-(D17-Pad1)") (class "Default")
      (node (ref "D17") (pin "1") (pinfunction "1_1") (pintype "bidirectional"))
    )
    (net (code "93") (name "unconnected-(D17-Pad7)") (class "Default")
      (node (ref "D17") (pin "7") (pinfunction "7_7") (pintype "bidirectional"))
    )
    (net (code "94") (name "unconnected-(D18-Pad1)") (class "Default")
      (node (ref "D18") (pin "1") (pinfunction "1_1") (pintype "bidirectional"))
    )
    (net (code "95") (name "unconnected-(D19-Pad1)") (class "Default")
      (node (ref "D19") (pin "1") (pinfunction "1_1") (pintype "bidirectional"))
    )
    (net (code "96") (name "unconnected-(D19-Pad7)") (class "Default")
      (node (ref "D19") (pin "7") (pinfunction "7_7") (pintype "bidirectional"))
    )
    (net (code "97") (name "unconnected-(D20-Pad1)") (class "Default")
      (node (ref "D20") (pin "1") (pinfunction "1_1") (pintype "bidirectional"))
    )
    (net (code "98") (name "unconnected-(D20-Pad7)") (class "Default")
      (node (ref "D20") (pin "7") (pinfunction "7_7") (pintype "bidirectional"))
    )
    (net (code "99") (name "unconnected-(E37#1-Pad7)") (class "Default")
      (node (ref "E37#1") (pin "7") (pinfunction "7_7") (pintype "bidirectional"))
    )
    (net (code "100") (name "unconnected-(E37#1-Pad8)") (class "Default")
      (node (ref "E37#1") (pin "8") (pinfunction "8_8") (pintype "bidirectional"))
    )
    (net (code "101") (name "unconnected-(E37#2-Pad7)") (class "Default")
      (node (ref "E37#2") (pin "7") (pinfunction "7_7") (pintype "bidirectional"))
    )
    (net (code "102") (name "unconnected-(E37#2-Pad8)") (class "Default")
      (node (ref "E37#2") (pin "8") (pinfunction "8_8") (pintype "bidirectional"))
    )
    (net (code "103") (name "unconnected-(KON6-Pad4)") (class "Default")
      (node (ref "KON6") (pin "4") (pinfunction "4_4") (pintype "bidirectional"))
    )
    (net (code "104") (name "unconnected-(KON6-Pad7)") (class "Default")
      (node (ref "KON6") (pin "7") (pinfunction "7_7") (pintype "bidirectional"))
    )
    (net (code "105") (name "unconnected-(T1-Pad1)") (class "Default")
      (node (ref "T1") (pin "1") (pinfunction "1_1") (pintype "bidirectional"))
    )
    (net (code "106") (name "unconnected-(T1-Pad2)") (class "Default")
      (node (ref "T1") (pin "2") (pinfunction "2_2") (pintype "bidirectional"))
    )
    (net (code "107") (name "unconnected-(T1-Pad3)") (class "Default")
      (node (ref "T1") (pin "3") (pinfunction "3_3") (pintype "bidirectional"))
    )
    (net (code "108") (name "unconnected-(T2-Pad1)") (class "Default")
      (node (ref "T2") (pin "1") (pinfunction "1_1") (pintype "bidirectional"))
    )
    (net (code "109") (name "unconnected-(T2-Pad2)") (class "Default")
      (node (ref "T2") (pin "2") (pinfunction "2_2") (pintype "bidirectional"))
    )
    (net (code "110") (name "unconnected-(T2-Pad3)") (class "Default")
      (node (ref "T2") (pin "3") (pinfunction "3_3") (pintype "bidirectional"))
    )
    (net (code "111") (name "unconnected-(T3-Pad1)") (class "Default")
      (node (ref "T3") (pin "1") (pinfunction "1_1") (pintype "bidirectional"))
    )
    (net (code "112") (name "unconnected-(T3-Pad2)") (class "Default")
      (node (ref "T3") (pin "2") (pinfunction "2_2") (pintype "bidirectional"))
    )
    (net (code "113") (name "unconnected-(T3-Pad3)") (class "Default")
      (node (ref "T3") (pin "3") (pinfunction "3_3") (pintype "bidirectional"))
    )
    (net (code "114") (name "unconnected-(T4-Pad1)") (class "Default")
      (node (ref "T4") (pin "1") (pinfunction "1_1") (pintype "bidirectional"))
    )
    (net (code "115") (name "unconnected-(T4-Pad2)") (class "Default")
      (node (ref "T4") (pin "2") (pinfunction "2_2") (pintype "bidirectional"))
    )
    (net (code "116") (name "unconnected-(T4-Pad3)") (class "Default")
      (node (ref "T4") (pin "3") (pinfunction "3_3") (pintype "bidirectional"))
    )
  )
)
